# LED_Micro.net
KiCad netlist of a schematic drawn in Altium Designer
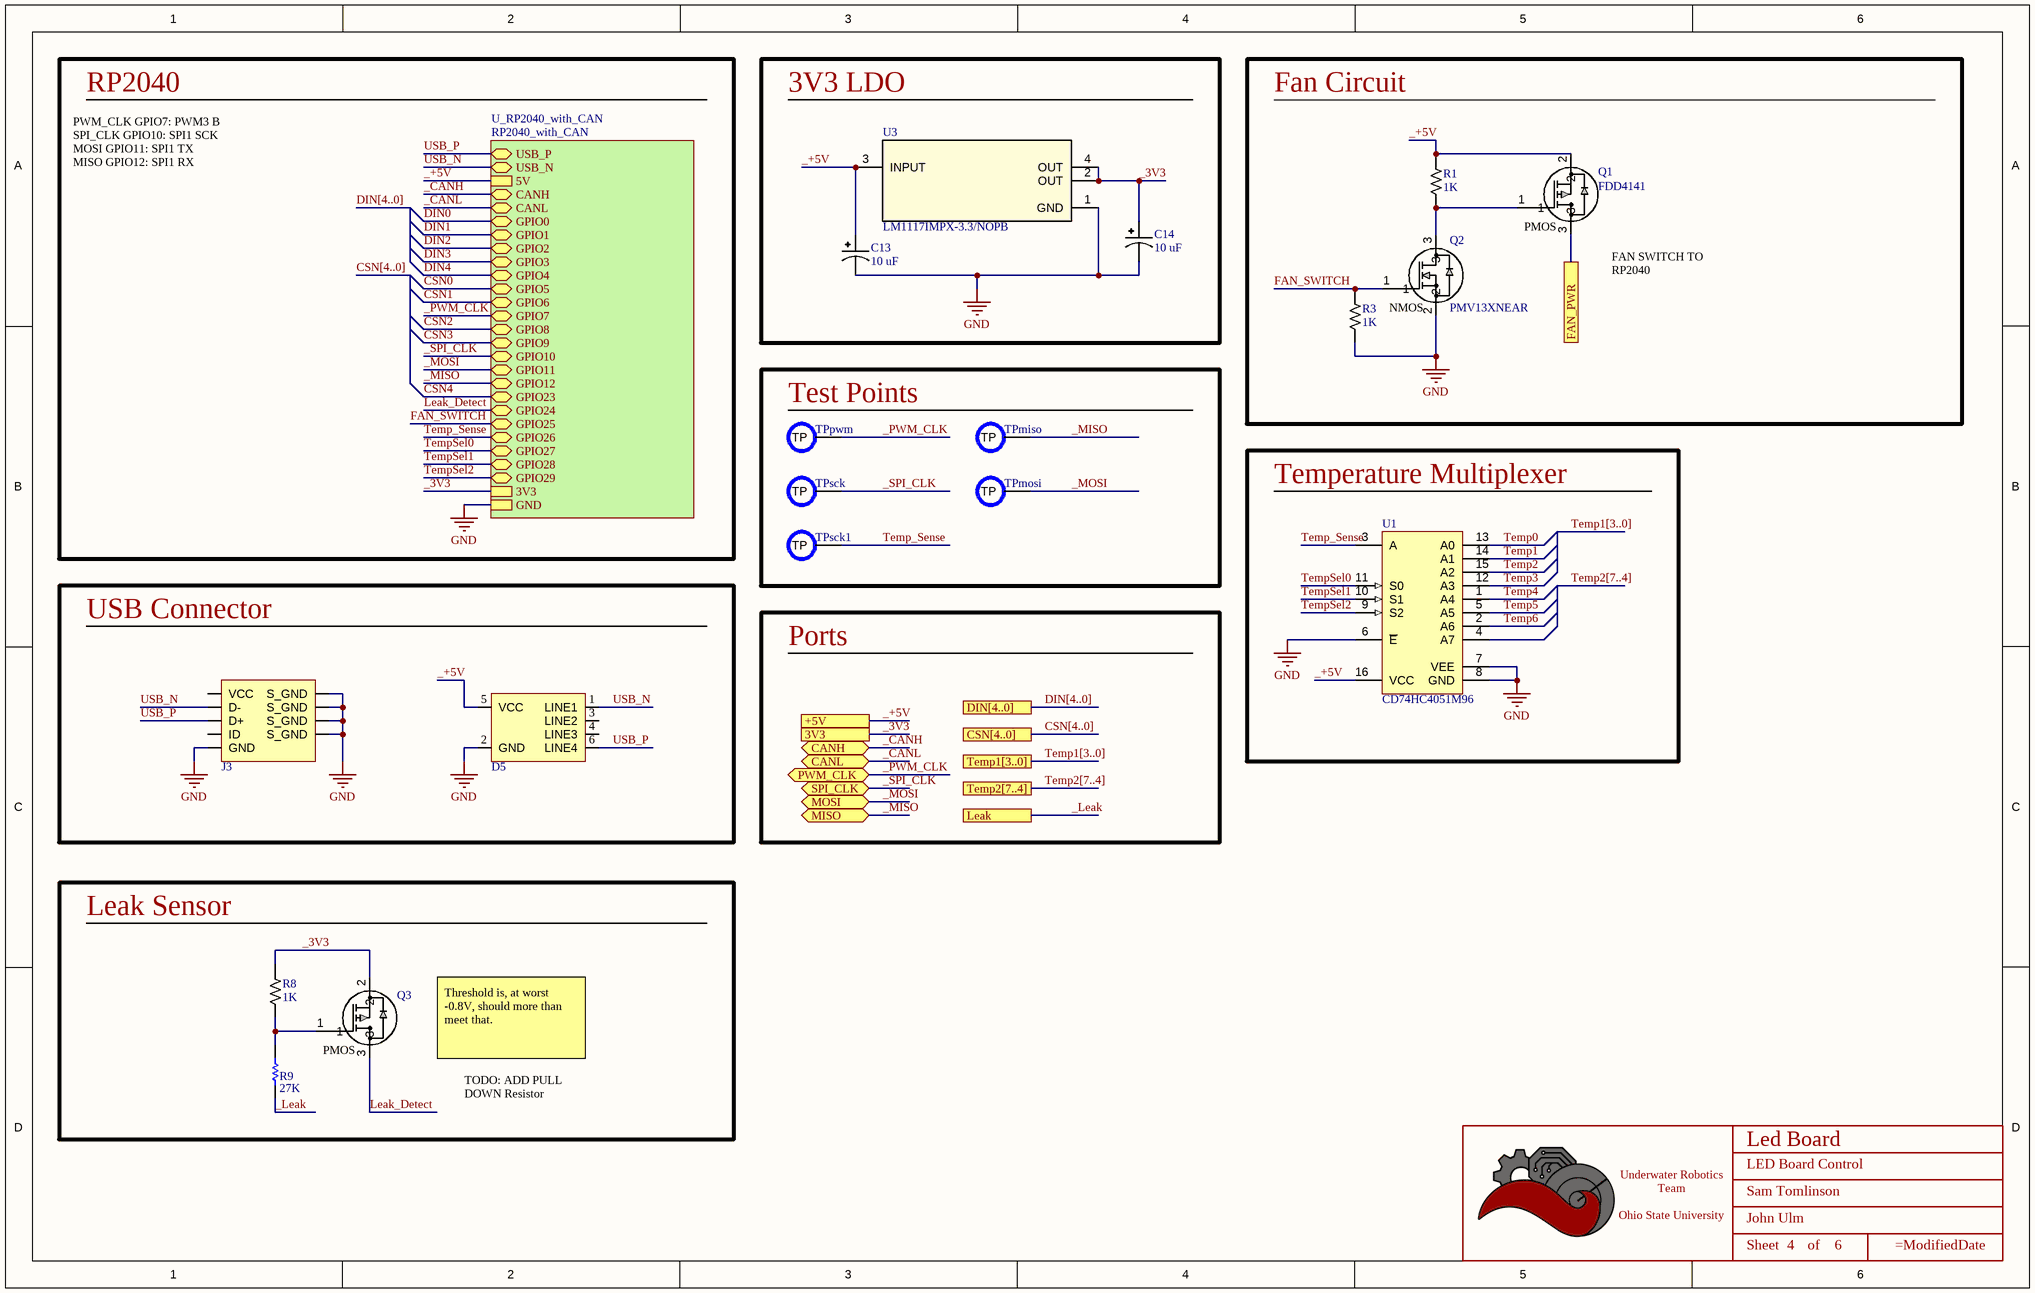
[diagram p0: LED_Micro.SchDoc]

(export (version "E")
  (design (tool "Eeschema 10.0.6"))
  (components
    (comp (ref "C13")
      (value "10uF Tantalum 16V")
      (footprint "CAPACITOR_1206 - POLAR")
      (description "Cap 10uF 16V +/-20%\r\nTantalum 1206")
      (fields
        (field (name "TOLERANCE") "+/- 10%")
        (field (name "VOLTAGE") "16V")
        (field (name "VALUE (UF)") "10 uF")
        (field (name "MADE BY") "Dylan T")
      )
      (libsource (lib "Capacitors") (part "CAPACITOR_10uF_1206_Tantalum_1"))
    )
    (comp (ref "C14")
      (value "10uF Tantalum 16V")
      (footprint "CAPACITOR_1206 - POLAR")
      (description "Cap 10uF 16V +/-20%\r\nTantalum 1206")
      (fields
        (field (name "TOLERANCE") "+/- 10%")
        (field (name "VOLTAGE") "16V")
        (field (name "VALUE (UF)") "10 uF")
        (field (name "MADE BY") "Dylan T")
      )
      (libsource (lib "Capacitors") (part "CAPACITOR_10uF_1206_Tantalum_1"))
    )
    (comp (ref "D5")
      (value "TVS DIODE 5VWM 25VC SOT23-6")
      (footprint "SOT 23-6L")
      (description "25V Clamp 6A (8/20µs) Ipp Tvs Diode Surface Mount SOT-23-6")
      (fields (field (name "MADE BY") "Robert Pafford"))
      (libsource (lib "Diodes") (part "RCLAMP0504S.TCT"))
    )
    (comp (ref "J3")
      (value "USB_MICRO R/A")
      (footprint "CONN_MINIUSB")
      (description "Amphenol Micro USB-B\r\nUSB2.0 5 Pin Right Angle SMD")
      (fields (field (name "MANUFACTURER") "Amphenol") (field (name "CREATED BY") "Flip B"))
      (libsource (lib "Connectors") (part "CONN_MICROUSB"))
    )
    (comp (ref "Q1")
      (value "FDD4141")
      (footprint "DPAK_ONS")
      (description "P-Channel 10.8A (Ta), 50A (Tc) 2.4W (Ta), 69W (Tc) Surface Mount D-PAK (TO-252AA)")
      (fields (field (name "CREATED BY") "Dylan T"))
      (libsource (lib "Transistors") (part "FDD4141"))
    )
    (comp (ref "Q2")
      (value "PMV13XNEAR")
      (footprint "SOT-23-3")
      (description "N-Channel 20 V 7.3A (Ta) 610mW (Ta), 8.3W (Tc) Surface Mount TO-236AB")
      (fields (field (name "CREATED BY") "Dylan T"))
      (libsource (lib "Transistors") (part "PMV13XNEAR"))
    )
    (comp (ref "Q3")
      (value "MOSFET P-CHANNEL 20V 4.7A SOT23")
      (footprint "SOT-23-3")
      (description "P-Channel 20 V 4.7A (Tc) 1.56W (Tc) Surface Mount SOT-23")
      (fields
        (field (name "MANUFACTURER_PART_NUMBER") "TSM500P02CX")
        (field (name "CREATED BY") "Robert Pafford")
      )
      (libsource (lib "Transistors") (part "TSM500P02CX"))
    )
    (comp (ref "R1")
      (value "1k Ohm 5% 1/8W")
      (footprint "RESISTOR_0603")
      (description "RES 1k OHM 5% 1/8W 0603")
      (fields
        (field (name "TOLERANCE") "+/- 5%")
        (field (name "VALUE  (OHMS)") "1K")
        (field (name "MADE BY") "Robert Pafford")
      )
      (libsource (lib "Resistors") (part "RESISTOR_1K_0603"))
    )
    (comp (ref "R3")
      (value "1k Ohm 5% 1/8W")
      (footprint "RESISTOR_0603")
      (description "RES 1k OHM 5% 1/8W 0603")
      (fields
        (field (name "TOLERANCE") "+/- 5%")
        (field (name "VALUE  (OHMS)") "1K")
        (field (name "MADE BY") "Robert Pafford")
      )
      (libsource (lib "Resistors") (part "RESISTOR_1K_0603"))
    )
    (comp (ref "R8")
      (value "1k Ohm 1% 1/16W")
      (footprint "RESISTOR_0402")
      (description "RES 1k OHM 1% 1/16W 0402")
      (fields
        (field (name "TOLERANCE") "+/- 1%")
        (field (name "VALUE  (OHMS)") "1K")
        (field (name "MADE BY") "Robert Pafford")
      )
      (libsource (lib "Resistors") (part "RESISTOR_1K_0402"))
    )
    (comp (ref "R9")
      (value "27K")
      (footprint "RESC1005X40X25ML05T05")
      (description "RES SMD 27K OHM 5% 1/10W 0402ERJ-2GEJ273X")
      (fields (field (name "MANUFACTURER") "Panasonic") (field (name "PART NUMBER") "ERJ-2GEJ273X"))
      (libsource (lib "Altium Content Vault") (part "RES"))
    )
    (comp (ref "TPmiso")
      (value "PCB Test Point")
      (footprint "TESTPOINT_1.2MM")
      (fields (field (name "MADE BY") "Robert Pafford"))
      (libsource (lib "Connectors") (part "TESTPOINT"))
    )
    (comp (ref "TPmosi")
      (value "PCB Test Point")
      (footprint "TESTPOINT_1.2MM")
      (fields (field (name "MADE BY") "Robert Pafford"))
      (libsource (lib "Connectors") (part "TESTPOINT"))
    )
    (comp (ref "TPpwm")
      (value "PCB Test Point")
      (footprint "TESTPOINT_1.2MM")
      (fields (field (name "MADE BY") "Robert Pafford"))
      (libsource (lib "Connectors") (part "TESTPOINT"))
    )
    (comp (ref "TPsck")
      (value "PCB Test Point")
      (footprint "TESTPOINT_1.2MM")
      (fields (field (name "MADE BY") "Robert Pafford"))
      (libsource (lib "Connectors") (part "TESTPOINT"))
    )
    (comp (ref "TPsck1")
      (value "PCB Test Point")
      (footprint "TESTPOINT_1.2MM")
      (fields (field (name "MADE BY") "Robert Pafford"))
      (libsource (lib "Connectors") (part "TESTPOINT"))
    )
    (comp (ref "U1")
      (value "CD74HC4051M96")
      (footprint "D0016A_M")
      (description "High Speed CMOS 8-Channel Analog Multiplexer/Demultiplexer, D0016A, LARGE T&R")
      (fields
        (field (name "GENERIC PART NUMBER") "CD74HC4051")
        (field (name "MANUFACTURER") "Texas Instruments")
      )
      (libsource (lib "Altium Content Vault") (part "TI-CD74HCX4051-16"))
    )
    (comp (ref "U3")
      (value "LM1117IMPX-3.3/NOPB")
      (footprint "SOT-223-4")
      (description "IC REG LIN 3.3V 800MA SOT223-4")
      (fields
        (field (name "PARTNUMBER") "LM1117IMP-3.3/NOPB")
        (field (name "MANUFACTURER") "Texas Instruments")
        (field (name "CREATED BY") "Dylan T")
      )
      (libsource (lib "Converter") (part "LM1117IMPX-3.3/NOPB"))
    )
  )
  (nets
    (net (code "21") (name "/FAN_PWR") (class "Default")
      (node (ref "Q1") (pin "3") (pinfunction "3_3") (pintype "passive"))
    )
    (net (code "22") (name "/FAN_SWITCH") (class "Default")
      (node (ref "Q2") (pin "1") (pinfunction "1_1") (pintype "passive"))
      (node (ref "R3") (pin "1") (pinfunction "1_1") (pintype "passive"))
    )
    (net (code "23") (name "/Leak_Detect") (class "Default")
      (node (ref "Q3") (pin "3") (pinfunction "3_3") (pintype "passive"))
    )
    (net (code "24") (name "/Temp0") (class "Default")
      (node (ref "U1") (pin "13") (pinfunction "A0_13") (pintype "passive"))
    )
    (net (code "25") (name "/Temp1") (class "Default")
      (node (ref "U1") (pin "14") (pinfunction "A1_14") (pintype "passive"))
    )
    (net (code "27") (name "/Temp2") (class "Default")
      (node (ref "U1") (pin "15") (pinfunction "A2_15") (pintype "passive"))
    )
    (net (code "29") (name "/Temp3") (class "Default")
      (node (ref "U1") (pin "12") (pinfunction "A3_12") (pintype "passive"))
    )
    (net (code "30") (name "/Temp4") (class "Default")
      (node (ref "U1") (pin "1") (pinfunction "A4_1") (pintype "passive"))
    )
    (net (code "31") (name "/Temp5") (class "Default")
      (node (ref "U1") (pin "5") (pinfunction "A5_5") (pintype "passive"))
    )
    (net (code "32") (name "/Temp6") (class "Default")
      (node (ref "U1") (pin "2") (pinfunction "A6_2") (pintype "passive"))
    )
    (net (code "33") (name "/TempSel0") (class "Default")
      (node (ref "U1") (pin "11") (pinfunction "S0_11") (pintype "input"))
    )
    (net (code "34") (name "/TempSel1") (class "Default")
      (node (ref "U1") (pin "10") (pinfunction "S1_10") (pintype "input"))
    )
    (net (code "35") (name "/TempSel2") (class "Default")
      (node (ref "U1") (pin "9") (pinfunction "S2_9") (pintype "input"))
    )
    (net (code "36") (name "/Temp_Sense") (class "Default")
      (node (ref "TPsck1") (pin "TP") (pinfunction "TP_TP") (pintype "passive"))
      (node (ref "U1") (pin "3") (pinfunction "A_3") (pintype "passive"))
    )
    (net (code "37") (name "/USB_N") (class "Default")
      (node (ref "D5") (pin "1") (pinfunction "LINE1_1") (pintype "passive"))
      (node (ref "J3") (pin "2") (pinfunction "D-_2") (pintype "passive"))
    )
    (net (code "38") (name "/USB_P") (class "Default")
      (node (ref "D5") (pin "6") (pinfunction "LINE4_6") (pintype "passive"))
      (node (ref "J3") (pin "3") (pinfunction "D+_3") (pintype "passive"))
    )
    (net (code "39") (name "/_+5V") (class "Default")
      (node (ref "C13") (pin "1") (pintype "passive"))
      (node (ref "D5") (pin "5") (pinfunction "VCC_5") (pintype "power_in"))
      (node (ref "Q1") (pin "2") (pinfunction "2_2") (pintype "passive"))
      (node (ref "R1") (pin "1") (pinfunction "1_1") (pintype "passive"))
      (node (ref "U1") (pin "16") (pinfunction "VCC_16") (pintype "power_in"))
      (node (ref "U3") (pin "3") (pinfunction "INPUT_3") (pintype "power_in"))
    )
    (net (code "40") (name "/_3V3") (class "Default")
      (node (ref "C14") (pin "1") (pintype "passive"))
      (node (ref "Q3") (pin "2") (pinfunction "2_2") (pintype "passive"))
      (node (ref "R8") (pin "1") (pinfunction "1_1") (pintype "passive"))
      (node (ref "U3") (pin "2") (pinfunction "OUT_2") (pintype "power_in"))
      (node (ref "U3") (pin "4") (pinfunction "OUT_4") (pintype "power_in"))
    )
    (net (code "43") (name "/_Leak") (class "Default")
      (node (ref "R9") (pin "1") (pinfunction "1_1") (pintype "passive"))
    )
    (net (code "44") (name "/_MISO") (class "Default")
      (node (ref "TPmiso") (pin "TP") (pinfunction "TP_TP") (pintype "passive"))
    )
    (net (code "45") (name "/_MOSI") (class "Default")
      (node (ref "TPmosi") (pin "TP") (pinfunction "TP_TP") (pintype "passive"))
    )
    (net (code "46") (name "/_PWM_CLK") (class "Default")
      (node (ref "TPpwm") (pin "TP") (pinfunction "TP_TP") (pintype "passive"))
    )
    (net (code "47") (name "/_SPI_CLK") (class "Default")
      (node (ref "TPsck") (pin "TP") (pinfunction "TP_TP") (pintype "passive"))
    )
    (net (code "48") (name "GND") (class "Default")
      (node (ref "C13") (pin "2") (pintype "passive"))
      (node (ref "C14") (pin "2") (pintype "passive"))
      (node (ref "D5") (pin "2") (pinfunction "GND_2") (pintype "power_in"))
      (node (ref "J3") (pin "5") (pinfunction "GND_5") (pintype "passive"))
      (node (ref "J3") (pin "6") (pinfunction "S_GND_6") (pintype "passive"))
      (node (ref "J3") (pin "7") (pinfunction "S_GND_7") (pintype "passive"))
      (node (ref "J3") (pin "8") (pinfunction "S_GND_8") (pintype "passive"))
      (node (ref "J3") (pin "9") (pinfunction "S_GND_9") (pintype "passive"))
      (node (ref "Q2") (pin "2") (pinfunction "2_2") (pintype "passive"))
      (node (ref "R3") (pin "2") (pinfunction "2_2") (pintype "passive"))
      (node (ref "U1") (pin "6") (pinfunction "~{E}_6") (pintype "passive"))
      (node (ref "U1") (pin "7") (pinfunction "VEE_7") (pintype "power_in"))
      (node (ref "U1") (pin "8") (pinfunction "GND_8") (pintype "power_in"))
      (node (ref "U3") (pin "1") (pinfunction "GND_1") (pintype "power_in"))
    )
    (net (code "49") (name "Net-(Q1-Pad1)") (class "Default")
      (node (ref "Q1") (pin "1") (pinfunction "1_1") (pintype "passive"))
      (node (ref "Q2") (pin "3") (pinfunction "3_3") (pintype "passive"))
      (node (ref "R1") (pin "2") (pinfunction "2_2") (pintype "passive"))
    )
    (net (code "50") (name "Net-(Q3-Pad1)") (class "Default")
      (node (ref "Q3") (pin "1") (pinfunction "1_1") (pintype "passive"))
      (node (ref "R8") (pin "2") (pinfunction "2_2") (pintype "passive"))
      (node (ref "R9") (pin "2") (pinfunction "2_2") (pintype "passive"))
    )
    (net (code "51") (name "unconnected-(D5-LINE2-Pad3)") (class "Default")
      (node (ref "D5") (pin "3") (pinfunction "LINE2_3") (pintype "passive"))
    )
    (net (code "52") (name "unconnected-(D5-LINE3-Pad4)") (class "Default")
      (node (ref "D5") (pin "4") (pinfunction "LINE3_4") (pintype "passive"))
    )
    (net (code "53") (name "unconnected-(J3-ID-Pad4)") (class "Default")
      (node (ref "J3") (pin "4") (pinfunction "ID_4") (pintype "passive"))
    )
    (net (code "54") (name "unconnected-(J3-VCC-Pad1)") (class "Default")
      (node (ref "J3") (pin "1") (pinfunction "VCC_1") (pintype "passive"))
    )
    (net (code "55") (name "unconnected-(U1-A7-Pad4)") (class "Default")
      (node (ref "U1") (pin "4") (pinfunction "A7_4") (pintype "passive"))
    )
  )
)
